# PWR_TPS62824-5-6-7.net
KiCad netlist of a schematic drawn in Altium Designer
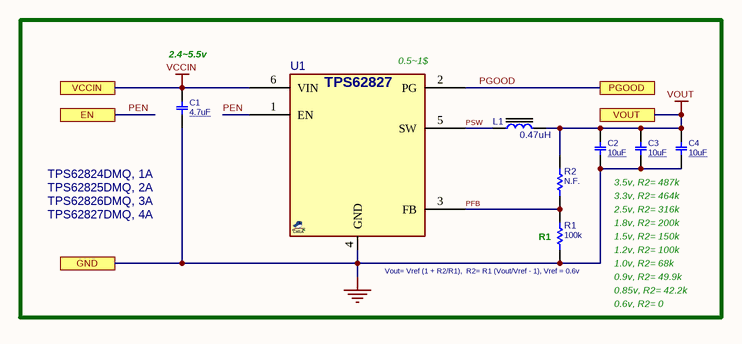
[diagram p0: PWR_TPS62824-5-6-7.SchDoc]

(export (version "E")
  (design (tool "Eeschema 10.0.6"))
  (components
    (comp (ref "C1")
      (value "4.7uF")
      (footprint "C0402A")
      (description "CAP, MLCC")
      (fields (field (name "MANF_P#") "GRM155R61A475MEAAD"))
      (libsource (lib "passive_smd") (part "CAP_SMD_MLCC"))
    )
    (comp (ref "C2")
      (value "10uF")
      (footprint "C0402A")
      (description "CAP, MLCC")
      (fields (field (name "MANF_P#") "CL05A106MP5NUNC"))
      (libsource (lib "passive_smd") (part "CAP_SMD_MLCC"))
    )
    (comp (ref "C3")
      (value "10uF")
      (footprint "C0402A")
      (description "CAP, MLCC")
      (fields (field (name "MANF_P#") "CL05A106MP5NUNC"))
      (libsource (lib "passive_smd") (part "CAP_SMD_MLCC"))
    )
    (comp (ref "C4")
      (value "10uF")
      (footprint "C0402A")
      (description "CAP, MLCC")
      (fields (field (name "MANF_P#") "CL05A106MP5NUNC"))
      (libsource (lib "passive_smd") (part "CAP_SMD_MLCC"))
    )
    (comp (ref "L1")
      (value "0.47uH")
      (footprint "L0805")
      (description "INDUCTOR, POWER, SMD")
      (fields (field (name "MANF") "Murata") (field (name "MANF_P#") "DFE201610E-R47M"))
      (libsource (lib "passive_smd") (part "INDPWR_SMD"))
    )
    (comp (ref "R1")
      (value "100k")
      (footprint "R0402A")
      (description "RESISTOR, SMD")
      (libsource (lib "passive_smd") (part "RES_SMD"))
    )
    (comp (ref "R2")
      (value "N.F.")
      (footprint "R0402A")
      (description "RESISTOR, SMD")
      (libsource (lib "passive_smd") (part "RES_SMD"))
    )
    (comp (ref "U1")
      (value "TPS62827")
      (footprint "SONHR50_6")
      (description "REG, Switching, Buck, 4A, ADJ, 2.2MHz, 2.4~5.5VIN, SONHR6")
      (fields (field (name "MANF_P#") "TPS62827DMQ") (field (name "MANF") "Texas Instruments"))
      (libsource (lib "pwr_switching_buck") (part "VREG_TPS62827_SONHR6"))
    )
  )
  (nets
    (net (code "1") (name "/PEN") (class "Default")
      (node (ref "U1") (pin "1") (pinfunction "EN_1") (pintype "passive"))
    )
    (net (code "2") (name "/PFB") (class "Default")
      (node (ref "R1") (pin "2") (pinfunction "2_2") (pintype "passive"))
      (node (ref "R2") (pin "1") (pinfunction "1_1") (pintype "passive"))
      (node (ref "U1") (pin "3") (pinfunction "FB_3") (pintype "passive"))
    )
    (net (code "3") (name "/PGOOD") (class "Default")
      (node (ref "U1") (pin "2") (pinfunction "PG_2") (pintype "passive"))
    )
    (net (code "4") (name "/PSW") (class "Default")
      (node (ref "L1") (pin "1") (pinfunction "1_1") (pintype "passive"))
      (node (ref "U1") (pin "5") (pinfunction "SW_5") (pintype "passive"))
    )
    (net (code "5") (name "GND") (class "Default")
      (node (ref "C1") (pin "2") (pinfunction "2_2") (pintype "passive"))
      (node (ref "C2") (pin "2") (pinfunction "2_2") (pintype "passive"))
      (node (ref "C3") (pin "2") (pinfunction "2_2") (pintype "passive"))
      (node (ref "C4") (pin "2") (pinfunction "2_2") (pintype "passive"))
      (node (ref "R1") (pin "1") (pinfunction "1_1") (pintype "passive"))
      (node (ref "U1") (pin "4") (pinfunction "GND_4") (pintype "passive"))
    )
    (net (code "6") (name "VCCIN") (class "Default")
      (node (ref "C1") (pin "1") (pinfunction "1_1") (pintype "passive"))
      (node (ref "U1") (pin "6") (pinfunction "VIN_6") (pintype "passive"))
    )
    (net (code "7") (name "VOUT") (class "Default")
      (node (ref "C2") (pin "1") (pinfunction "1_1") (pintype "passive"))
      (node (ref "C3") (pin "1") (pinfunction "1_1") (pintype "passive"))
      (node (ref "C4") (pin "1") (pinfunction "1_1") (pintype "passive"))
      (node (ref "L1") (pin "2") (pinfunction "2_2") (pintype "passive"))
      (node (ref "R2") (pin "2") (pinfunction "2_2") (pintype "passive"))
    )
  )
)
